# 5-Way_Tactile_Switch_BOB_v11.net
KiCad netlist of a schematic drawn in EAGLE
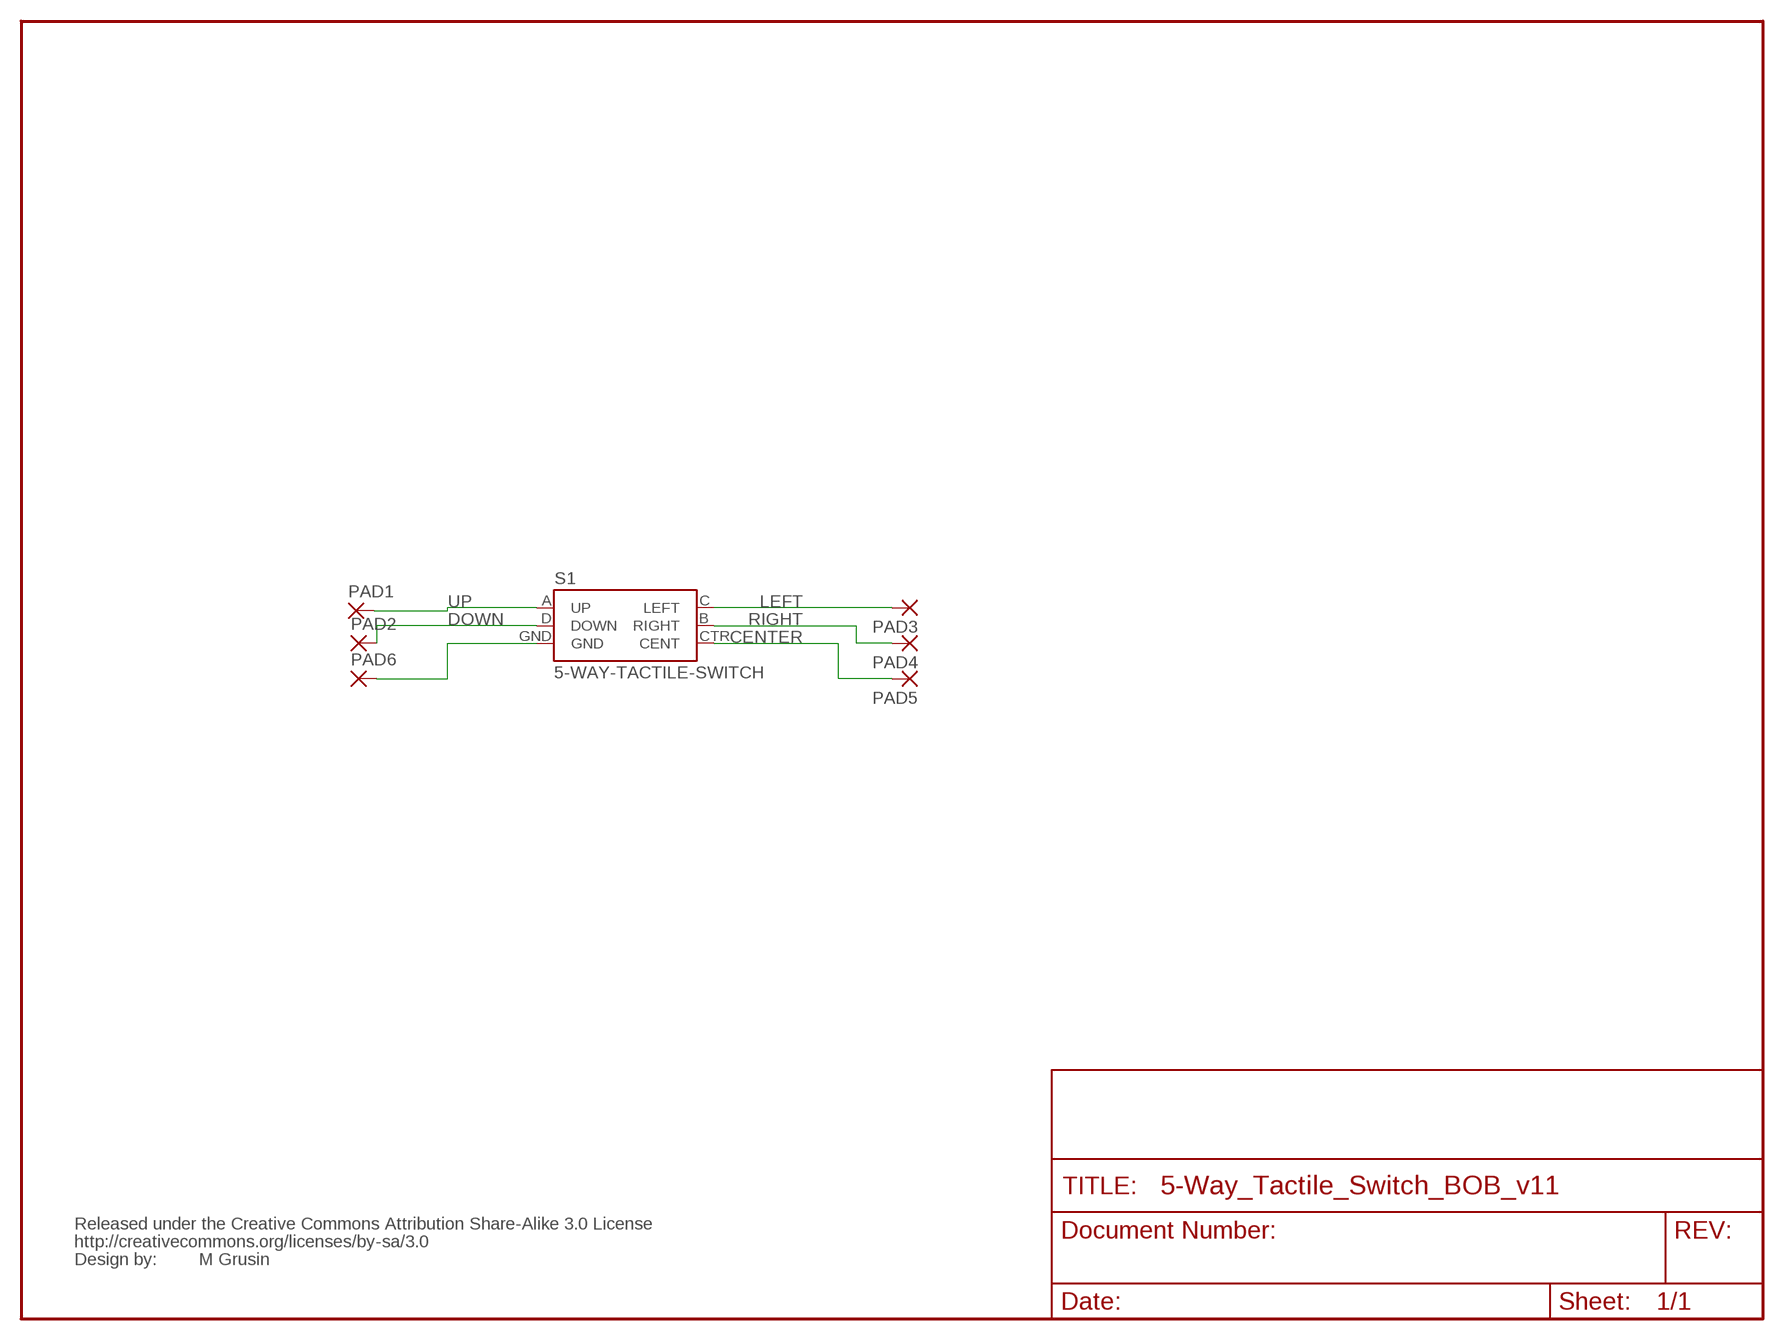
[diagram p0: schematic, sheet 1]

(export (version "E")
  (design (tool "Eeschema 10.0.6"))
  (components
    (comp (ref "PAD1")
      (value "SMD2")
      (footprint "eagle-import:SMD1,27-2,54")
      (libsource (lib "eagle-import") (part "SMD2"))
    )
    (comp (ref "PAD2")
      (value "SMD2")
      (footprint "eagle-import:SMD1,27-2,54")
      (libsource (lib "eagle-import") (part "SMD2"))
    )
    (comp (ref "PAD3")
      (value "SMD2")
      (footprint "eagle-import:SMD1,27-2,54")
      (libsource (lib "eagle-import") (part "SMD2"))
    )
    (comp (ref "PAD4")
      (value "SMD2")
      (footprint "eagle-import:SMD1,27-2,54")
      (libsource (lib "eagle-import") (part "SMD2"))
    )
    (comp (ref "PAD5")
      (value "SMD2")
      (footprint "eagle-import:SMD1,27-2,54")
      (libsource (lib "eagle-import") (part "SMD2"))
    )
    (comp (ref "PAD6")
      (value "SMD2")
      (footprint "eagle-import:SMD1,27-2,54")
      (libsource (lib "eagle-import") (part "SMD2"))
    )
    (comp (ref "S1")
      (value "5-WAY-TACTILE-SWITCH")
      (footprint "eagle-import:JOYSTICK_MINI")
      (libsource (lib "eagle-import") (part "JOYSTICK_MINI"))
    )
    (comp (ref "U$2")
      (value "CREATIVE_COMMONS")
      (footprint "eagle-import:CREATIVE_COMMONS")
      (libsource (lib "eagle-import") (part "CREATIVE_COMMONS"))
    )
  )
  (nets
    (net (code "1") (name "/CENTER") (class "Default")
      (node (ref "PAD5") (pin "1") (pinfunction "P_1") (pintype "passive"))
      (node (ref "S1") (pin "CTR") (pinfunction "CENT_CTR") (pintype "bidirectional"))
    )
    (net (code "2") (name "/DOWN") (class "Default")
      (node (ref "PAD2") (pin "1") (pinfunction "P_1") (pintype "passive"))
      (node (ref "S1") (pin "D") (pinfunction "DOWN_D") (pintype "bidirectional"))
    )
    (net (code "3") (name "/LEFT") (class "Default")
      (node (ref "PAD3") (pin "1") (pinfunction "P_1") (pintype "passive"))
      (node (ref "S1") (pin "C") (pinfunction "LEFT_C") (pintype "bidirectional"))
    )
    (net (code "4") (name "/RIGHT") (class "Default")
      (node (ref "PAD4") (pin "1") (pinfunction "P_1") (pintype "passive"))
      (node (ref "S1") (pin "B") (pinfunction "RIGHT_B") (pintype "bidirectional"))
    )
    (net (code "5") (name "/UP") (class "Default")
      (node (ref "PAD1") (pin "1") (pinfunction "P_1") (pintype "passive"))
      (node (ref "S1") (pin "A") (pinfunction "UP_A") (pintype "bidirectional"))
    )
    (net (code "6") (name "Net-(PAD6-P)") (class "Default")
      (node (ref "PAD6") (pin "1") (pinfunction "P_1") (pintype "passive"))
      (node (ref "S1") (pin "GND") (pinfunction "GND_GND") (pintype "bidirectional"))
    )
  )
)
